# Schema.net
KiCad netlist of a schematic drawn in Altium Designer
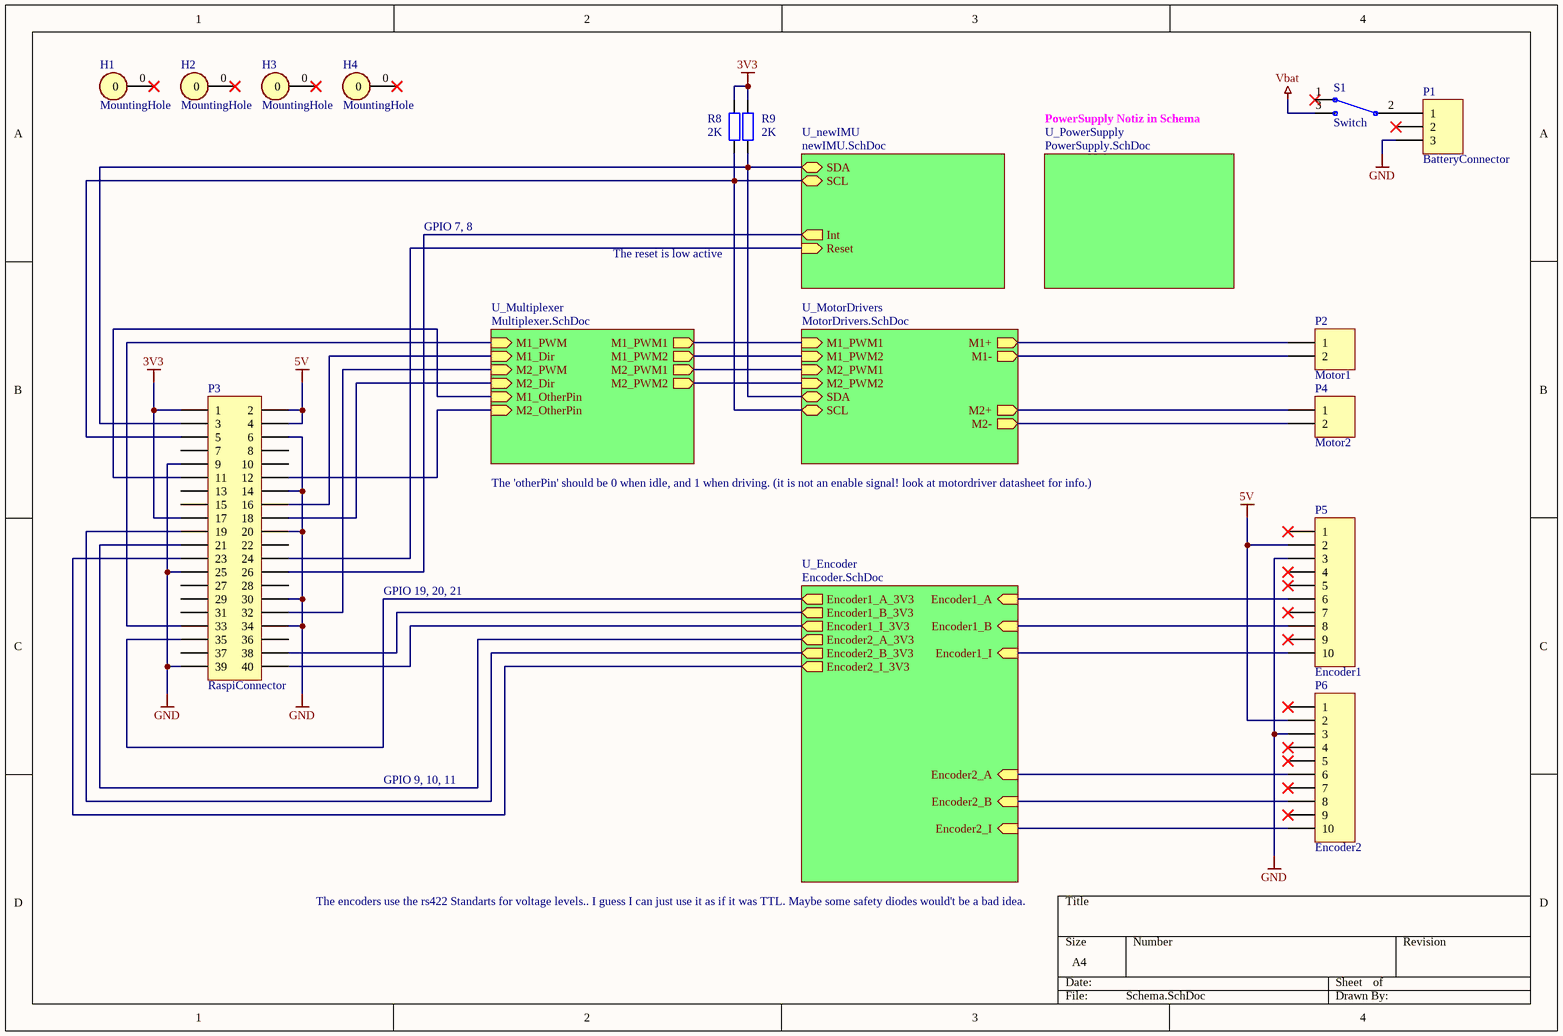
[diagram p0: Schema.SchDoc]

(export (version "E")
  (design (tool "Eeschema 10.0.6"))
  (components
    (comp (ref "H1")
      (value "MountingHole")
      (footprint "MountingHole")
      (libsource (lib "SchematicLib") (part "MountingHole"))
    )
    (comp (ref "H2")
      (value "MountingHole")
      (footprint "MountingHole")
      (libsource (lib "SchematicLib") (part "MountingHole"))
    )
    (comp (ref "H3")
      (value "MountingHole")
      (footprint "MountingHole")
      (libsource (lib "SchematicLib") (part "MountingHole"))
    )
    (comp (ref "H4")
      (value "MountingHole")
      (footprint "MountingHole")
      (libsource (lib "SchematicLib") (part "MountingHole"))
    )
    (comp (ref "P1")
      (value "BatteryConnector")
      (footprint "BatteryConnector")
      (description "Header, 3-Pin")
      (fields (field (name "PUBLISHER") "Altium Limited"))
      (libsource (lib "Miscellaneous Connectors") (part "Header 3"))
    )
    (comp (ref "P2")
      (value "Motor1")
      (footprint "MotorConnector")
      (description "Header, 2-Pin")
      (fields (field (name "PUBLISHER") "Altium Limited"))
      (libsource (lib "Miscellaneous Connectors") (part "Header 2"))
    )
    (comp (ref "P3")
      (value "RaspiConnector")
      (footprint "HDR2X20")
      (description "Header, 20-Pin, Dual row")
      (fields (field (name "PUBLISHER") "Altium Limited"))
      (libsource (lib "Miscellaneous Connectors") (part "Header 20X2"))
    )
    (comp (ref "P4")
      (value "Motor2")
      (footprint "MotorConnector")
      (description "Header, 2-Pin")
      (fields (field (name "PUBLISHER") "Altium Limited"))
      (libsource (lib "Miscellaneous Connectors") (part "Header 2"))
    )
    (comp (ref "P5")
      (value "Encoder1")
      (footprint "EncoderConnector")
      (description "Header, 10-Pin")
      (fields (field (name "PUBLISHER") "Altium Limited"))
      (libsource (lib "Miscellaneous Connectors") (part "Header 10"))
    )
    (comp (ref "P6")
      (value "Encoder2")
      (footprint "EncoderConnector")
      (description "Header, 10-Pin")
      (fields (field (name "PUBLISHER") "Altium Limited"))
      (libsource (lib "Miscellaneous Connectors") (part "Header 10"))
    )
    (comp (ref "R8")
      (value "2K")
      (footprint "0805_Lorin")
      (description "Resistor")
      (fields (field (name "Comment") "Res2") (field (name "PUBLISHER") "Altium Limited"))
      (libsource (lib "Miscellaneous Devices") (part "Res2"))
    )
    (comp (ref "R9")
      (value "2K")
      (footprint "0805_Lorin")
      (description "Resistor")
      (fields (field (name "Comment") "Res2") (field (name "PUBLISHER") "Altium Limited"))
      (libsource (lib "Miscellaneous Devices") (part "Res2"))
    )
    (comp (ref "S1") (value "Switch") (footprint "Switch") (libsource (lib "SchematicLib") (part "Switch")))
  )
  (nets
    (net (code "1") (name "/Encoder1_A") (class "Default")
      (node (ref "P5") (pin "6") (pinfunction "6_6") (pintype "passive"))
    )
    (net (code "2") (name "/Encoder1_A_3V3") (class "Default")
      (node (ref "P3") (pin "35") (pinfunction "35_35") (pintype "passive"))
    )
    (net (code "3") (name "/Encoder1_B") (class "Default")
      (node (ref "P5") (pin "8") (pinfunction "8_8") (pintype "passive"))
    )
    (net (code "4") (name "/Encoder1_B_3V3") (class "Default")
      (node (ref "P3") (pin "38") (pinfunction "38_38") (pintype "passive"))
    )
    (net (code "5") (name "/Encoder1_I") (class "Default")
      (node (ref "P5") (pin "10") (pinfunction "10_10") (pintype "passive"))
    )
    (net (code "6") (name "/Encoder1_I_3V3") (class "Default")
      (node (ref "P3") (pin "40") (pinfunction "40_40") (pintype "passive"))
    )
    (net (code "7") (name "/Encoder2_A") (class "Default")
      (node (ref "P6") (pin "6") (pinfunction "6_6") (pintype "passive"))
    )
    (net (code "8") (name "/Encoder2_A_3V3") (class "Default")
      (node (ref "P3") (pin "21") (pinfunction "21_21") (pintype "passive"))
    )
    (net (code "9") (name "/Encoder2_B") (class "Default")
      (node (ref "P6") (pin "8") (pinfunction "8_8") (pintype "passive"))
    )
    (net (code "10") (name "/Encoder2_B_3V3") (class "Default")
      (node (ref "P3") (pin "19") (pinfunction "19_19") (pintype "passive"))
    )
    (net (code "11") (name "/Encoder2_I") (class "Default")
      (node (ref "P6") (pin "10") (pinfunction "10_10") (pintype "passive"))
    )
    (net (code "12") (name "/Encoder2_I_3V3") (class "Default")
      (node (ref "P3") (pin "23") (pinfunction "23_23") (pintype "passive"))
    )
    (net (code "13") (name "/Int") (class "Default")
      (node (ref "P3") (pin "26") (pinfunction "26_26") (pintype "passive"))
    )
    (net (code "14") (name "/M1+") (class "Default")
      (node (ref "P2") (pin "1") (pinfunction "1_1") (pintype "passive"))
    )
    (net (code "15") (name "/M1-") (class "Default")
      (node (ref "P2") (pin "2") (pinfunction "2_2") (pintype "passive"))
    )
    (net (code "16") (name "/M1_Dir") (class "Default")
      (node (ref "P3") (pin "16") (pinfunction "16_16") (pintype "passive"))
    )
    (net (code "17") (name "/M1_OtherPin") (class "Default")
      (node (ref "P3") (pin "11") (pinfunction "11_11") (pintype "passive"))
    )
    (net (code "18") (name "/M1_PWM") (class "Default")
      (node (ref "P3") (pin "33") (pinfunction "33_33") (pintype "passive"))
    )
    (net (code "21") (name "/M2+") (class "Default")
      (node (ref "P4") (pin "1") (pinfunction "1_1") (pintype "passive"))
    )
    (net (code "22") (name "/M2-") (class "Default")
      (node (ref "P4") (pin "2") (pinfunction "2_2") (pintype "passive"))
    )
    (net (code "23") (name "/M2_Dir") (class "Default")
      (node (ref "P3") (pin "18") (pinfunction "18_18") (pintype "passive"))
    )
    (net (code "24") (name "/M2_OtherPin") (class "Default")
      (node (ref "P3") (pin "12") (pinfunction "12_12") (pintype "passive"))
    )
    (net (code "25") (name "/M2_PWM") (class "Default")
      (node (ref "P3") (pin "32") (pinfunction "32_32") (pintype "passive"))
    )
    (net (code "28") (name "/Reset") (class "Default")
      (node (ref "P3") (pin "24") (pinfunction "24_24") (pintype "passive"))
    )
    (net (code "29") (name "/SCL") (class "Default")
      (node (ref "P3") (pin "5") (pinfunction "5_5") (pintype "passive"))
      (node (ref "R8") (pin "1") (pinfunction "1_1") (pintype "passive"))
    )
    (net (code "30") (name "/SDA") (class "Default")
      (node (ref "P3") (pin "3") (pinfunction "3_3") (pintype "passive"))
      (node (ref "R9") (pin "1") (pinfunction "1_1") (pintype "passive"))
    )
    (net (code "31") (name "3V3") (class "Default")
      (node (ref "P3") (pin "1") (pinfunction "1_1") (pintype "passive"))
      (node (ref "P3") (pin "17") (pinfunction "17_17") (pintype "passive"))
      (node (ref "R8") (pin "2") (pinfunction "2_2") (pintype "passive"))
      (node (ref "R9") (pin "2") (pinfunction "2_2") (pintype "passive"))
    )
    (net (code "32") (name "5V") (class "Default")
      (node (ref "P3") (pin "2") (pinfunction "2_2") (pintype "passive"))
      (node (ref "P3") (pin "4") (pinfunction "4_4") (pintype "passive"))
      (node (ref "P5") (pin "2") (pinfunction "2_2") (pintype "passive"))
      (node (ref "P6") (pin "2") (pinfunction "2_2") (pintype "passive"))
    )
    (net (code "33") (name "GND") (class "Default")
      (node (ref "P1") (pin "3") (pinfunction "3_3") (pintype "passive"))
      (node (ref "P3") (pin "14") (pinfunction "14_14") (pintype "passive"))
      (node (ref "P3") (pin "20") (pinfunction "20_20") (pintype "passive"))
      (node (ref "P3") (pin "25") (pinfunction "25_25") (pintype "passive"))
      (node (ref "P3") (pin "30") (pinfunction "30_30") (pintype "passive"))
      (node (ref "P3") (pin "34") (pinfunction "34_34") (pintype "passive"))
      (node (ref "P3") (pin "39") (pinfunction "39_39") (pintype "passive"))
      (node (ref "P3") (pin "6") (pinfunction "6_6") (pintype "passive"))
      (node (ref "P3") (pin "9") (pinfunction "9_9") (pintype "passive"))
      (node (ref "P5") (pin "3") (pinfunction "3_3") (pintype "passive"))
      (node (ref "P6") (pin "3") (pinfunction "3_3") (pintype "passive"))
    )
    (net (code "34") (name "Net-(P1-Pad1)") (class "Default")
      (node (ref "P1") (pin "1") (pinfunction "1_1") (pintype "passive"))
      (node (ref "S1") (pin "2") (pinfunction "2_2") (pintype "passive"))
    )
    (net (code "35") (name "Vbat") (class "Default")
      (node (ref "S1") (pin "3") (pinfunction "3_3") (pintype "passive"))
    )
    (net (code "36") (name "unconnected-(H1-Pad0)") (class "Default")
      (node (ref "H1") (pin "0") (pinfunction "0_0") (pintype "passive+no_connect"))
    )
    (net (code "37") (name "unconnected-(H2-Pad0)") (class "Default")
      (node (ref "H2") (pin "0") (pinfunction "0_0") (pintype "passive+no_connect"))
    )
    (net (code "38") (name "unconnected-(H3-Pad0)") (class "Default")
      (node (ref "H3") (pin "0") (pinfunction "0_0") (pintype "passive+no_connect"))
    )
    (net (code "39") (name "unconnected-(H4-Pad0)") (class "Default")
      (node (ref "H4") (pin "0") (pinfunction "0_0") (pintype "passive+no_connect"))
    )
    (net (code "40") (name "unconnected-(P1-Pad2)") (class "Default")
      (node (ref "P1") (pin "2") (pinfunction "2_2") (pintype "passive+no_connect"))
    )
    (net (code "41") (name "unconnected-(P3-Pad7)") (class "Default")
      (node (ref "P3") (pin "7") (pinfunction "7_7") (pintype "passive"))
    )
    (net (code "42") (name "unconnected-(P3-Pad8)") (class "Default")
      (node (ref "P3") (pin "8") (pinfunction "8_8") (pintype "passive"))
    )
    (net (code "43") (name "unconnected-(P3-Pad10)") (class "Default")
      (node (ref "P3") (pin "10") (pinfunction "10_10") (pintype "passive"))
    )
    (net (code "44") (name "unconnected-(P3-Pad13)") (class "Default")
      (node (ref "P3") (pin "13") (pinfunction "13_13") (pintype "passive"))
    )
    (net (code "45") (name "unconnected-(P3-Pad15)") (class "Default")
      (node (ref "P3") (pin "15") (pinfunction "15_15") (pintype "passive"))
    )
    (net (code "46") (name "unconnected-(P3-Pad22)") (class "Default")
      (node (ref "P3") (pin "22") (pinfunction "22_22") (pintype "passive"))
    )
    (net (code "47") (name "unconnected-(P3-Pad27)") (class "Default")
      (node (ref "P3") (pin "27") (pinfunction "27_27") (pintype "passive"))
    )
    (net (code "48") (name "unconnected-(P3-Pad28)") (class "Default")
      (node (ref "P3") (pin "28") (pinfunction "28_28") (pintype "passive"))
    )
    (net (code "49") (name "unconnected-(P3-Pad29)") (class "Default")
      (node (ref "P3") (pin "29") (pinfunction "29_29") (pintype "passive"))
    )
    (net (code "50") (name "unconnected-(P3-Pad31)") (class "Default")
      (node (ref "P3") (pin "31") (pinfunction "31_31") (pintype "passive"))
    )
    (net (code "51") (name "unconnected-(P3-Pad36)") (class "Default")
      (node (ref "P3") (pin "36") (pinfunction "36_36") (pintype "passive"))
    )
    (net (code "52") (name "unconnected-(P3-Pad37)") (class "Default")
      (node (ref "P3") (pin "37") (pinfunction "37_37") (pintype "passive"))
    )
    (net (code "53") (name "unconnected-(P5-Pad1)") (class "Default")
      (node (ref "P5") (pin "1") (pinfunction "1_1") (pintype "passive+no_connect"))
    )
    (net (code "54") (name "unconnected-(P5-Pad4)") (class "Default")
      (node (ref "P5") (pin "4") (pinfunction "4_4") (pintype "passive+no_connect"))
    )
    (net (code "55") (name "unconnected-(P5-Pad5)") (class "Default")
      (node (ref "P5") (pin "5") (pinfunction "5_5") (pintype "passive+no_connect"))
    )
    (net (code "56") (name "unconnected-(P5-Pad7)") (class "Default")
      (node (ref "P5") (pin "7") (pinfunction "7_7") (pintype "passive+no_connect"))
    )
    (net (code "57") (name "unconnected-(P5-Pad9)") (class "Default")
      (node (ref "P5") (pin "9") (pinfunction "9_9") (pintype "passive+no_connect"))
    )
    (net (code "58") (name "unconnected-(P6-Pad1)") (class "Default")
      (node (ref "P6") (pin "1") (pinfunction "1_1") (pintype "passive+no_connect"))
    )
    (net (code "59") (name "unconnected-(P6-Pad4)") (class "Default")
      (node (ref "P6") (pin "4") (pinfunction "4_4") (pintype "passive+no_connect"))
    )
    (net (code "60") (name "unconnected-(P6-Pad5)") (class "Default")
      (node (ref "P6") (pin "5") (pinfunction "5_5") (pintype "passive+no_connect"))
    )
    (net (code "61") (name "unconnected-(P6-Pad7)") (class "Default")
      (node (ref "P6") (pin "7") (pinfunction "7_7") (pintype "passive+no_connect"))
    )
    (net (code "62") (name "unconnected-(P6-Pad9)") (class "Default")
      (node (ref "P6") (pin "9") (pinfunction "9_9") (pintype "passive+no_connect"))
    )
    (net (code "63") (name "unconnected-(S1-Pad1)") (class "Default")
      (node (ref "S1") (pin "1") (pinfunction "1_1") (pintype "passive+no_connect"))
    )
  )
)
